# outdoor_plata.net
KiCad netlist of a schematic drawn in Altium Designer
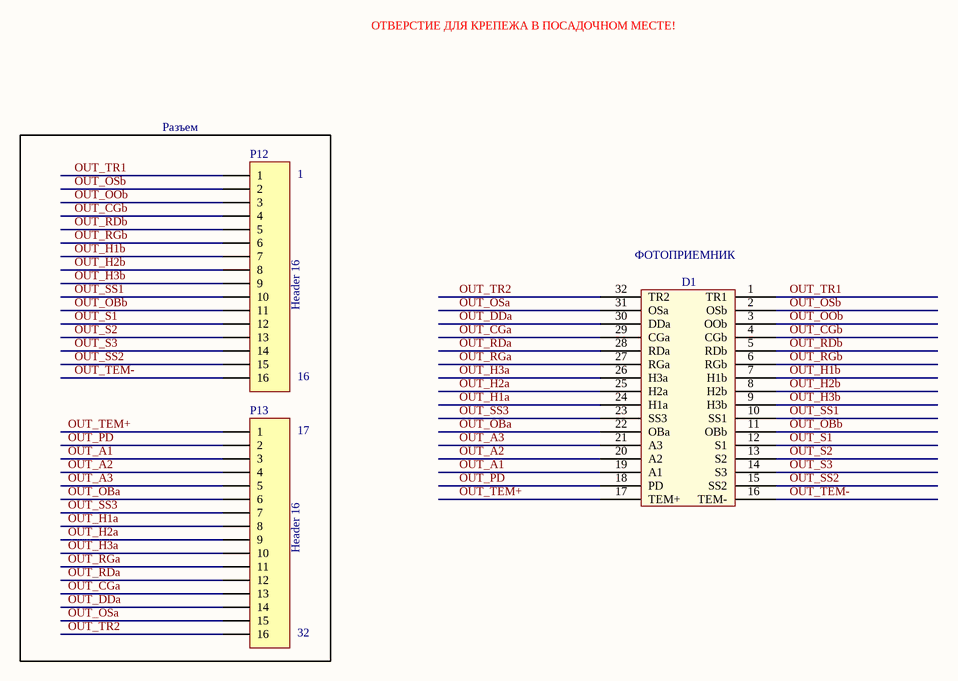
[diagram p0: outdoor_plata.SchDoc]

(export (version "E")
  (design (tool "Eeschema 10.0.6"))
  (components
    (comp (ref "D1")
      (value "FPPZ 1024M")
      (footprint "FPPZ_1024M")
      (libsource (lib "Schlib") (part "FPPZ 1024M"))
    )
    (comp (ref "P12")
      (value "Header 16")
      (footprint "HDR1X16")
      (description "Header, 16-Pin")
      (fields (field (name "PUBLISHER") "Altium Limited"))
      (libsource (lib "Miscellaneous Connectors") (part "Header 16"))
    )
    (comp (ref "P13")
      (value "Header 16")
      (footprint "HDR1X16")
      (description "Header, 16-Pin")
      (fields (field (name "PUBLISHER") "Altium Limited"))
      (libsource (lib "Miscellaneous Connectors") (part "Header 16"))
    )
  )
  (nets
    (net (code "1") (name "/OUT_A1") (class "Default")
      (node (ref "D1") (pin "19") (pinfunction "A1_19") (pintype "passive"))
      (node (ref "P13") (pin "3") (pinfunction "3_3") (pintype "passive"))
    )
    (net (code "2") (name "/OUT_A2") (class "Default")
      (node (ref "D1") (pin "20") (pinfunction "A2_20") (pintype "passive"))
      (node (ref "P13") (pin "4") (pinfunction "4_4") (pintype "passive"))
    )
    (net (code "3") (name "/OUT_A3") (class "Default")
      (node (ref "D1") (pin "21") (pinfunction "A3_21") (pintype "passive"))
      (node (ref "P13") (pin "5") (pinfunction "5_5") (pintype "passive"))
    )
    (net (code "4") (name "/OUT_CGa") (class "Default")
      (node (ref "D1") (pin "29") (pinfunction "CGa_29") (pintype "passive"))
      (node (ref "P13") (pin "13") (pinfunction "13_13") (pintype "passive"))
    )
    (net (code "5") (name "/OUT_CGb") (class "Default")
      (node (ref "D1") (pin "4") (pinfunction "CGb_4") (pintype "passive"))
      (node (ref "P12") (pin "4") (pinfunction "4_4") (pintype "passive"))
    )
    (net (code "6") (name "/OUT_DDa") (class "Default")
      (node (ref "D1") (pin "30") (pinfunction "DDa_30") (pintype "passive"))
      (node (ref "P13") (pin "14") (pinfunction "14_14") (pintype "passive"))
    )
    (net (code "7") (name "/OUT_H1a") (class "Default")
      (node (ref "D1") (pin "24") (pinfunction "H1a_24") (pintype "passive"))
      (node (ref "P13") (pin "8") (pinfunction "8_8") (pintype "passive"))
    )
    (net (code "8") (name "/OUT_H1b") (class "Default")
      (node (ref "D1") (pin "7") (pinfunction "H1b_7") (pintype "passive"))
      (node (ref "P12") (pin "7") (pinfunction "7_7") (pintype "passive"))
    )
    (net (code "9") (name "/OUT_H2a") (class "Default")
      (node (ref "D1") (pin "25") (pinfunction "H2a_25") (pintype "passive"))
      (node (ref "P13") (pin "9") (pinfunction "9_9") (pintype "passive"))
    )
    (net (code "10") (name "/OUT_H2b") (class "Default")
      (node (ref "D1") (pin "8") (pinfunction "H2b_8") (pintype "passive"))
      (node (ref "P12") (pin "8") (pinfunction "8_8") (pintype "passive"))
    )
    (net (code "11") (name "/OUT_H3a") (class "Default")
      (node (ref "D1") (pin "26") (pinfunction "H3a_26") (pintype "passive"))
      (node (ref "P13") (pin "10") (pinfunction "10_10") (pintype "passive"))
    )
    (net (code "12") (name "/OUT_H3b") (class "Default")
      (node (ref "D1") (pin "9") (pinfunction "H3b_9") (pintype "passive"))
      (node (ref "P12") (pin "9") (pinfunction "9_9") (pintype "passive"))
    )
    (net (code "13") (name "/OUT_OBa") (class "Default")
      (node (ref "D1") (pin "22") (pinfunction "OBa_22") (pintype "passive"))
      (node (ref "P13") (pin "6") (pinfunction "6_6") (pintype "passive"))
    )
    (net (code "14") (name "/OUT_OBb") (class "Default")
      (node (ref "D1") (pin "11") (pinfunction "OBb_11") (pintype "passive"))
      (node (ref "P12") (pin "11") (pinfunction "11_11") (pintype "passive"))
    )
    (net (code "15") (name "/OUT_OOb") (class "Default")
      (node (ref "D1") (pin "3") (pinfunction "OOb_3") (pintype "passive"))
      (node (ref "P12") (pin "3") (pinfunction "3_3") (pintype "passive"))
    )
    (net (code "16") (name "/OUT_OSa") (class "Default")
      (node (ref "D1") (pin "31") (pinfunction "OSa_31") (pintype "passive"))
      (node (ref "P13") (pin "15") (pinfunction "15_15") (pintype "passive"))
    )
    (net (code "17") (name "/OUT_OSb") (class "Default")
      (node (ref "D1") (pin "2") (pinfunction "OSb_2") (pintype "passive"))
      (node (ref "P12") (pin "2") (pinfunction "2_2") (pintype "passive"))
    )
    (net (code "18") (name "/OUT_PD") (class "Default")
      (node (ref "D1") (pin "18") (pinfunction "PD_18") (pintype "passive"))
      (node (ref "P13") (pin "2") (pinfunction "2_2") (pintype "passive"))
    )
    (net (code "19") (name "/OUT_RDa") (class "Default")
      (node (ref "D1") (pin "28") (pinfunction "RDa_28") (pintype "passive"))
      (node (ref "P13") (pin "12") (pinfunction "12_12") (pintype "passive"))
    )
    (net (code "20") (name "/OUT_RDb") (class "Default")
      (node (ref "D1") (pin "5") (pinfunction "RDb_5") (pintype "passive"))
      (node (ref "P12") (pin "5") (pinfunction "5_5") (pintype "passive"))
    )
    (net (code "21") (name "/OUT_RGa") (class "Default")
      (node (ref "D1") (pin "27") (pinfunction "RGa_27") (pintype "passive"))
      (node (ref "P13") (pin "11") (pinfunction "11_11") (pintype "passive"))
    )
    (net (code "22") (name "/OUT_RGb") (class "Default")
      (node (ref "D1") (pin "6") (pinfunction "RGb_6") (pintype "passive"))
      (node (ref "P12") (pin "6") (pinfunction "6_6") (pintype "passive"))
    )
    (net (code "23") (name "/OUT_S1") (class "Default")
      (node (ref "D1") (pin "12") (pinfunction "S1_12") (pintype "passive"))
      (node (ref "P12") (pin "12") (pinfunction "12_12") (pintype "passive"))
    )
    (net (code "24") (name "/OUT_S2") (class "Default")
      (node (ref "D1") (pin "13") (pinfunction "S2_13") (pintype "passive"))
      (node (ref "P12") (pin "13") (pinfunction "13_13") (pintype "passive"))
    )
    (net (code "25") (name "/OUT_S3") (class "Default")
      (node (ref "D1") (pin "14") (pinfunction "S3_14") (pintype "passive"))
      (node (ref "P12") (pin "14") (pinfunction "14_14") (pintype "passive"))
    )
    (net (code "26") (name "/OUT_SS1") (class "Default")
      (node (ref "D1") (pin "10") (pinfunction "SS1_10") (pintype "passive"))
      (node (ref "P12") (pin "10") (pinfunction "10_10") (pintype "passive"))
    )
    (net (code "27") (name "/OUT_SS2") (class "Default")
      (node (ref "D1") (pin "15") (pinfunction "SS2_15") (pintype "passive"))
      (node (ref "P12") (pin "15") (pinfunction "15_15") (pintype "passive"))
    )
    (net (code "28") (name "/OUT_SS3") (class "Default")
      (node (ref "D1") (pin "23") (pinfunction "SS3_23") (pintype "passive"))
      (node (ref "P13") (pin "7") (pinfunction "7_7") (pintype "passive"))
    )
    (net (code "29") (name "/OUT_TEM+") (class "Default")
      (node (ref "D1") (pin "17") (pinfunction "TEM+_17") (pintype "passive"))
      (node (ref "P13") (pin "1") (pinfunction "1_1") (pintype "passive"))
    )
    (net (code "30") (name "/OUT_TEM-") (class "Default")
      (node (ref "D1") (pin "16") (pinfunction "TEM-_16") (pintype "passive"))
      (node (ref "P12") (pin "16") (pinfunction "16_16") (pintype "passive"))
    )
    (net (code "31") (name "/OUT_TR1") (class "Default")
      (node (ref "D1") (pin "1") (pinfunction "TR1_1") (pintype "passive"))
      (node (ref "P12") (pin "1") (pinfunction "1_1") (pintype "passive"))
    )
    (net (code "32") (name "/OUT_TR2") (class "Default")
      (node (ref "D1") (pin "32") (pinfunction "TR2_32") (pintype "passive"))
      (node (ref "P13") (pin "16") (pinfunction "16_16") (pintype "passive"))
    )
  )
)
